# VX.net
KiCad netlist of a schematic drawn in Altium Designer
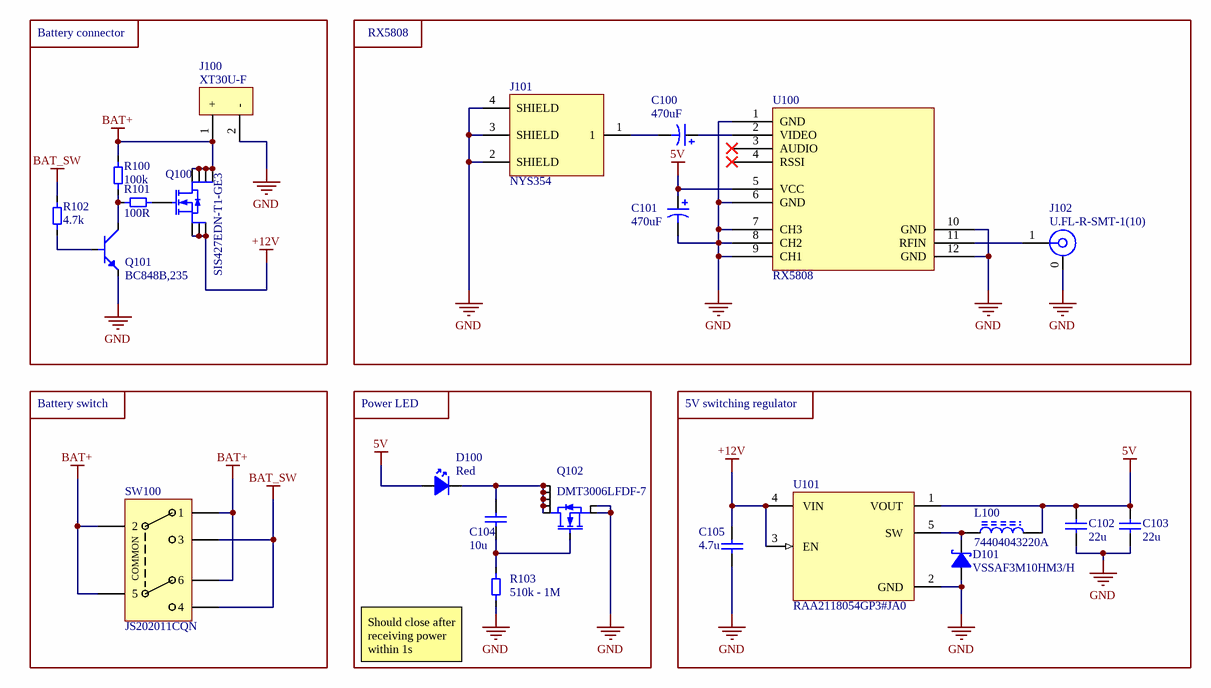
[diagram p0: VX.SchDoc]

(export (version "E")
  (design (tool "Eeschema 10.0.6"))
  (components
    (comp (ref "C100")
      (value "T55D477M6R3C0015")
      (footprint "T521X337M016ATE050-Footprint-1")
      (description "Cap Tant Polymer 470uF 6.3VDC D CASE 20% (7.3 X 4.3 X 2.8mm) SMD 7343-31 0.015 Ohm 105C T/R")
      (fields
        (field (name "VOLTAGE") "6.3V")
        (field (name "TOLERANCE") "20%")
        (field (name "CAPACITANCE") "470uF")
      )
      (libsource (lib "Krakul Vault") (part "GENERIC TANT CAP"))
    )
    (comp (ref "C101")
      (value "T55D477M6R3C0015")
      (footprint "T521X337M016ATE050-Footprint-1")
      (description "Cap Tant Polymer 470uF 6.3VDC D CASE 20% (7.3 X 4.3 X 2.8mm) SMD 7343-31 0.015 Ohm 105C T/R")
      (fields
        (field (name "VOLTAGE") "6.3V")
        (field (name "TOLERANCE") "20%")
        (field (name "CAPACITANCE") "470uF")
      )
      (libsource (lib "Krakul Vault") (part "GENERIC TANT CAP"))
    )
    (comp (ref "C102")
      (value "22u")
      (footprint "MLCC_1206_M")
      (description "MLCC, 1206, 22u, 10%, 16V, X5R")
      (fields (field (name "MANUFACTURER") "Any") (field (name "VOLTAGE") "16V"))
      (libsource (lib "Krakul Vault") (part "CAPACITOR_NONPOL_IEC"))
    )
    (comp (ref "C103")
      (value "22u")
      (footprint "MLCC_1206_M")
      (description "MLCC, 1206, 22u, 10%, 16V, X5R")
      (fields (field (name "MANUFACTURER") "Any") (field (name "VOLTAGE") "16V"))
      (libsource (lib "Krakul Vault") (part "CAPACITOR_NONPOL_IEC"))
    )
    (comp (ref "C104")
      (value "10u")
      (footprint "MLCC_0805_M")
      (description "MLCC, 0805, 10u, 10%, 50V, X5R")
      (fields (field (name "TOLERANCE") "10%") (field (name "VOLTAGE") "50V"))
      (libsource (lib "Krakul Vault") (part "CAPACITOR_NONPOL_IEC"))
    )
    (comp (ref "C105")
      (value "4.7u")
      (footprint "MLCC_1206_M")
      (description "MLCC, 1206, 4.7u, 10%, 35V, X5R")
      (fields (field (name "VOLTAGE") "35V") (field (name "TOLERANCE") "10%"))
      (libsource (lib "Krakul Vault") (part "CAPACITOR_NONPOL_IEC"))
    )
    (comp (ref "D100")
      (value "Red")
      (footprint "0603 RED LED")
      (description "Generic red 0603 LED")
      (fields (field (name "PART NUMBER") "Any Red 0603 LED") (field (name "MANUFACTURER") "Any"))
      (libsource (lib "Krakul Vault") (part "LED generic"))
    )
    (comp (ref "D101")
      (value "VSSAF3M10HM3/H")
      (footprint "VSSAF3M10HM3_H-Footprint-1")
      (description "Rectifier Diode, Schottky, 1 Phase, 1 Element, 2.3A, 100V V(RRM), Silicon, DO-221AC")
      (libsource (lib "Krakul Vault") (part "Schottky generic 2 pins"))
    )
    (comp (ref "J100")
      (value "XT30U-F")
      (footprint "XT30U-F")
      (description "Power Connector")
      (fields (field (name "MANUFACTURER") "AMASS"))
      (libsource (lib "Krakul Vault") (part "XT30U-F-Symbol-1"))
    )
    (comp (ref "J101")
      (value "NYS354")
      (footprint "NYS354")
      (description "RCA Phono Connector Shielded Right Angle Solder Pin")
      (fields (field (name "MANUFACTURER") "REAN"))
      (libsource (lib "Krakul Vault") (part "NYS354"))
    )
    (comp (ref "J102")
      (value "U.FL-R-SMT-1(10)")
      (footprint "FP-U_FL-R-SMT-1_10-MFG")
      (description "RF CONNECTOR RF Connector, 1 Contact(s), Male, Board Mount, Surface Mount Terminal, Receptacle")
      (fields (field (name "MANUFACTURER") "Hirose Electric Co Ltd"))
      (libsource (lib "Krakul Vault") (part "U.FL-R-SMT-1(10)"))
    )
    (comp (ref "L100")
      (value "74404043220A")
      (footprint "WE-LQS_4025")
      (description "General Purpose Inductor, 22uH, 20%, 1 Element, Nickel-zinc Ferrite-Core, SMD, 1616")
      (fields (field (name "MANUFACTURER") "Wurth Elektronik"))
      (libsource (lib "Krakul Vault") (part "INDUCTOR_SHIELDED"))
    )
    (comp (ref "Q100")
      (value "SIS427EDN-T1-GE3")
      (footprint "Copy of TPN2R304PL,L1Q-Footprint-1")
      (description "Trans MOSFET P-CH 30V 15A 8-Pin PowerPAK EP T/R")
      (fields (field (name "MANUFACTURER") "Vishay Siliconix"))
      (libsource (lib "Krakul Vault") (part "P-CH MOSFET 8-pin v2"))
    )
    (comp (ref "Q101")
      (value "BC848B,235")
      (footprint "SOT-23-3")
      (description "Small Signal Bipolar Transistor, 0.1A I(C), 30V V(BR)CEO, 1-Element, NPN, Silicon, TO-236AB")
      (fields (field (name "MANUFACTURER") "Nexperia"))
      (libsource (lib "Krakul Vault") (part "NPN SOT23"))
    )
    (comp (ref "Q102")
      (value "DMT3006LFDF-7")
      (footprint "DMT3006LFDF-7")
      (description "Mosfet, N-Ch, 30V, 14.1A, Udfn2020 Rohs Compliant: Yes")
      (fields (field (name "MANUFACTURER") "Diodes Incorporated"))
      (libsource (lib "Krakul Vault") (part "N-CH MOSFET"))
    )
    (comp (ref "R100")
      (value "100k")
      (footprint "Resistor_0603_M")
      (description "Resistor, 0603, 100k, 1%, 1/10W")
      (fields (field (name "TOLERANCE") "1%") (field (name "MANUFACTURER") "Any"))
      (libsource (lib "Krakul Vault") (part "RESISTOR_GENERIC_IEC"))
    )
    (comp (ref "R101")
      (value "100R")
      (footprint "Resistor_0603_M")
      (description "Resistor, 0603, 100R, 1%, 1/10W")
      (fields (field (name "POWER") "100mW") (field (name "MANUFACTURER") "Any"))
      (libsource (lib "Krakul Vault") (part "RESISTOR_GENERIC_IEC"))
    )
    (comp (ref "R102")
      (value "4.7k")
      (footprint "Resistor_0603_M")
      (description "Resistor, 0603, 4.7k, 1%, 1/10W")
      (fields (field (name "MANUFACTURER") "Any") (field (name "POWER") "100mW"))
      (libsource (lib "Krakul Vault") (part "RESISTOR_GENERIC_IEC"))
    )
    (comp (ref "R103")
      (value "510k")
      (footprint "Resistor_0603_M")
      (description "Resistor, 0603, 510k, 1%, 1/10W")
      (fields (field (name "TOLERANCE") "1%") (field (name "MANUFACTURER") "Any"))
      (libsource (lib "Krakul Vault") (part "RESISTOR_GENERIC_IEC"))
    )
    (comp (ref "SW100")
      (value "JS202011CQN")
      (footprint "FP-JS202011CQN-MFG")
      (description "Slide Switch, 1 Positions, Dpdt, Latched, 0.3A, 6Vdc, 6 Pcb Hole Cnt, Solder Terminal, Through")
      (fields (field (name "MANUFACTURER") "C&K"))
      (libsource (lib "Krakul Vault") (part "JS202011CQN-Symbol-1"))
    )
    (comp (ref "U100")
      (value "RX5808")
      (footprint "RX5808-Footprint-1")
      (description "RX5808 Video Module")
      (fields (field (name "MANUFACTURER") "Unknown"))
      (libsource (lib "Krakul Vault") (part "RX5808"))
    )
    (comp (ref "U101")
      (value "RAA2118054GP3#JA0")
      (footprint "P5_064B_MFG")
      (description "Switching Regulator, Current-mode, 0.3A, 230kHz Switching Freq-Max, PDSO5")
      (fields (field (name "MANUFACTURER") "Renesas / Intersil"))
      (libsource (lib "Krakul Vault") (part "04ef17e7ed04f306c00cc4b237f44d7"))
    )
  )
  (nets
    (net (code "1") (name "+12V") (class "Default")
      (node (ref "C105") (pin "2") (pinfunction "2_2") (pintype "passive"))
      (node (ref "Q100") (pin "1") (pinfunction "S_1") (pintype "passive"))
      (node (ref "Q100") (pin "2") (pinfunction "S_2") (pintype "passive"))
      (node (ref "Q100") (pin "3") (pinfunction "S_3") (pintype "passive"))
      (node (ref "U101") (pin "3") (pinfunction "EN_3") (pintype "input"))
      (node (ref "U101") (pin "4") (pinfunction "VIN_4") (pintype "power_in"))
    )
    (net (code "2") (name "5V") (class "Default")
      (node (ref "C101") (pin "1") (pinfunction "1_1") (pintype "passive"))
      (node (ref "C102") (pin "2") (pinfunction "2_2") (pintype "passive"))
      (node (ref "C103") (pin "2") (pinfunction "2_2") (pintype "passive"))
      (node (ref "D100") (pin "2") (pinfunction "A_2") (pintype "passive"))
      (node (ref "L100") (pin "2") (pinfunction "2_2") (pintype "passive"))
      (node (ref "U100") (pin "5") (pinfunction "VCC_5") (pintype "passive"))
      (node (ref "U101") (pin "1") (pinfunction "VOUT_1") (pintype "power_in"))
    )
    (net (code "3") (name "BAT+") (class "Default")
      (node (ref "J100") (pin "1") (pinfunction "+_1") (pintype "passive"))
      (node (ref "Q100") (pin "5") (pinfunction "D_5") (pintype "passive"))
      (node (ref "Q100") (pin "6") (pinfunction "D_6") (pintype "passive"))
      (node (ref "Q100") (pin "7") (pinfunction "D_7") (pintype "passive"))
      (node (ref "Q100") (pin "8") (pinfunction "D_8") (pintype "passive"))
      (node (ref "R100") (pin "2") (pinfunction "2_2") (pintype "passive"))
      (node (ref "SW100") (pin "1") (pinfunction "1_1") (pintype "passive"))
      (node (ref "SW100") (pin "2") (pinfunction "2_2") (pintype "passive"))
      (node (ref "SW100") (pin "5") (pinfunction "5_5") (pintype "passive"))
      (node (ref "SW100") (pin "6") (pinfunction "6_6") (pintype "passive"))
    )
    (net (code "4") (name "BAT_SW") (class "Default")
      (node (ref "R102") (pin "2") (pinfunction "2_2") (pintype "passive"))
      (node (ref "SW100") (pin "3") (pinfunction "3_3") (pintype "passive"))
      (node (ref "SW100") (pin "4") (pinfunction "4_4") (pintype "passive"))
    )
    (net (code "5") (name "GND") (class "Default")
      (node (ref "C101") (pin "2") (pinfunction "2_2") (pintype "passive"))
      (node (ref "C102") (pin "1") (pinfunction "1_1") (pintype "passive"))
      (node (ref "C103") (pin "1") (pinfunction "1_1") (pintype "passive"))
      (node (ref "C105") (pin "1") (pinfunction "1_1") (pintype "passive"))
      (node (ref "D101") (pin "2") (pinfunction "A_2") (pintype "passive"))
      (node (ref "J100") (pin "2") (pinfunction "-_2") (pintype "passive"))
      (node (ref "J101") (pin "2") (pinfunction "SHIELD_2") (pintype "passive"))
      (node (ref "J101") (pin "3") (pinfunction "SHIELD_3") (pintype "passive"))
      (node (ref "J101") (pin "4") (pinfunction "SHIELD_4") (pintype "passive"))
      (node (ref "J102") (pin "0") (pinfunction "GND_0") (pintype "passive"))
      (node (ref "Q101") (pin "2") (pinfunction "E_2") (pintype "power_in"))
      (node (ref "Q102") (pin "4") (pinfunction "S_4") (pintype "passive"))
      (node (ref "Q102") (pin "8") (pinfunction "S_8") (pintype "passive"))
      (node (ref "R103") (pin "1") (pinfunction "1_1") (pintype "passive"))
      (node (ref "U100") (pin "1") (pinfunction "GND_1") (pintype "passive"))
      (node (ref "U100") (pin "10") (pinfunction "GND_10") (pintype "passive"))
      (node (ref "U100") (pin "12") (pinfunction "GND_12") (pintype "passive"))
      (node (ref "U100") (pin "6") (pinfunction "GND_6") (pintype "passive"))
      (node (ref "U100") (pin "7") (pinfunction "CH3_7") (pintype "passive"))
      (node (ref "U100") (pin "8") (pinfunction "CH2_8") (pintype "passive"))
      (node (ref "U100") (pin "9") (pinfunction "CH1_9") (pintype "passive"))
      (node (ref "U101") (pin "2") (pinfunction "GND_2") (pintype "power_in"))
    )
    (net (code "6") (name "Net-(C100-Pad2)") (class "Default")
      (node (ref "C100") (pin "2") (pinfunction "2_2") (pintype "passive"))
      (node (ref "J101") (pin "1") (pinfunction "1_1") (pintype "passive"))
    )
    (net (code "7") (name "Net-(D100-C)") (class "Default")
      (node (ref "C104") (pin "2") (pinfunction "2_2") (pintype "passive"))
      (node (ref "D100") (pin "1") (pinfunction "C_1") (pintype "passive"))
      (node (ref "Q102") (pin "1") (pinfunction "D_1") (pintype "passive"))
      (node (ref "Q102") (pin "2") (pinfunction "D_2") (pintype "passive"))
      (node (ref "Q102") (pin "5") (pinfunction "D_5") (pintype "passive"))
      (node (ref "Q102") (pin "6") (pinfunction "D_6") (pintype "passive"))
      (node (ref "Q102") (pin "7") (pinfunction "D_7") (pintype "passive"))
    )
    (net (code "8") (name "Net-(D101-C)") (class "Default")
      (node (ref "D101") (pin "1") (pinfunction "C_1") (pintype "passive"))
      (node (ref "L100") (pin "1") (pinfunction "1_1") (pintype "passive"))
      (node (ref "U101") (pin "5") (pinfunction "SW_5") (pintype "passive"))
    )
    (net (code "9") (name "Net-(J102-SIG)") (class "Default")
      (node (ref "J102") (pin "1") (pinfunction "SIG_1") (pintype "passive"))
      (node (ref "U100") (pin "11") (pinfunction "RFIN_11") (pintype "passive"))
    )
    (net (code "10") (name "Net-(Q100-G)") (class "Default")
      (node (ref "Q100") (pin "4") (pinfunction "G_4") (pintype "passive"))
      (node (ref "R101") (pin "2") (pinfunction "2_2") (pintype "passive"))
    )
    (net (code "11") (name "Net-(Q101-B)") (class "Default")
      (node (ref "Q101") (pin "1") (pinfunction "B_1") (pintype "power_in"))
      (node (ref "R102") (pin "1") (pinfunction "1_1") (pintype "passive"))
    )
    (net (code "12") (name "Net-(Q101-C)") (class "Default")
      (node (ref "Q101") (pin "3") (pinfunction "C_3") (pintype "power_in"))
      (node (ref "R100") (pin "1") (pinfunction "1_1") (pintype "passive"))
      (node (ref "R101") (pin "1") (pinfunction "1_1") (pintype "passive"))
    )
    (net (code "13") (name "Net-(Q102-G)") (class "Default")
      (node (ref "C104") (pin "1") (pinfunction "1_1") (pintype "passive"))
      (node (ref "Q102") (pin "3") (pinfunction "G_3") (pintype "passive"))
      (node (ref "R103") (pin "2") (pinfunction "2_2") (pintype "passive"))
    )
    (net (code "14") (name "Net-(U100-VIDEO)") (class "Default")
      (node (ref "C100") (pin "1") (pinfunction "1_1") (pintype "passive"))
      (node (ref "U100") (pin "2") (pinfunction "VIDEO_2") (pintype "passive"))
    )
    (net (code "15") (name "unconnected-(U100-AUDIO-Pad3)") (class "Default")
      (node (ref "U100") (pin "3") (pinfunction "AUDIO_3") (pintype "passive+no_connect"))
    )
    (net (code "16") (name "unconnected-(U100-RSSI-Pad4)") (class "Default")
      (node (ref "U100") (pin "4") (pinfunction "RSSI_4") (pintype "passive+no_connect"))
    )
  )
)
